# XMOS_TSBOARD_IV.net
KiCad netlist of a schematic drawn in Altium Designer
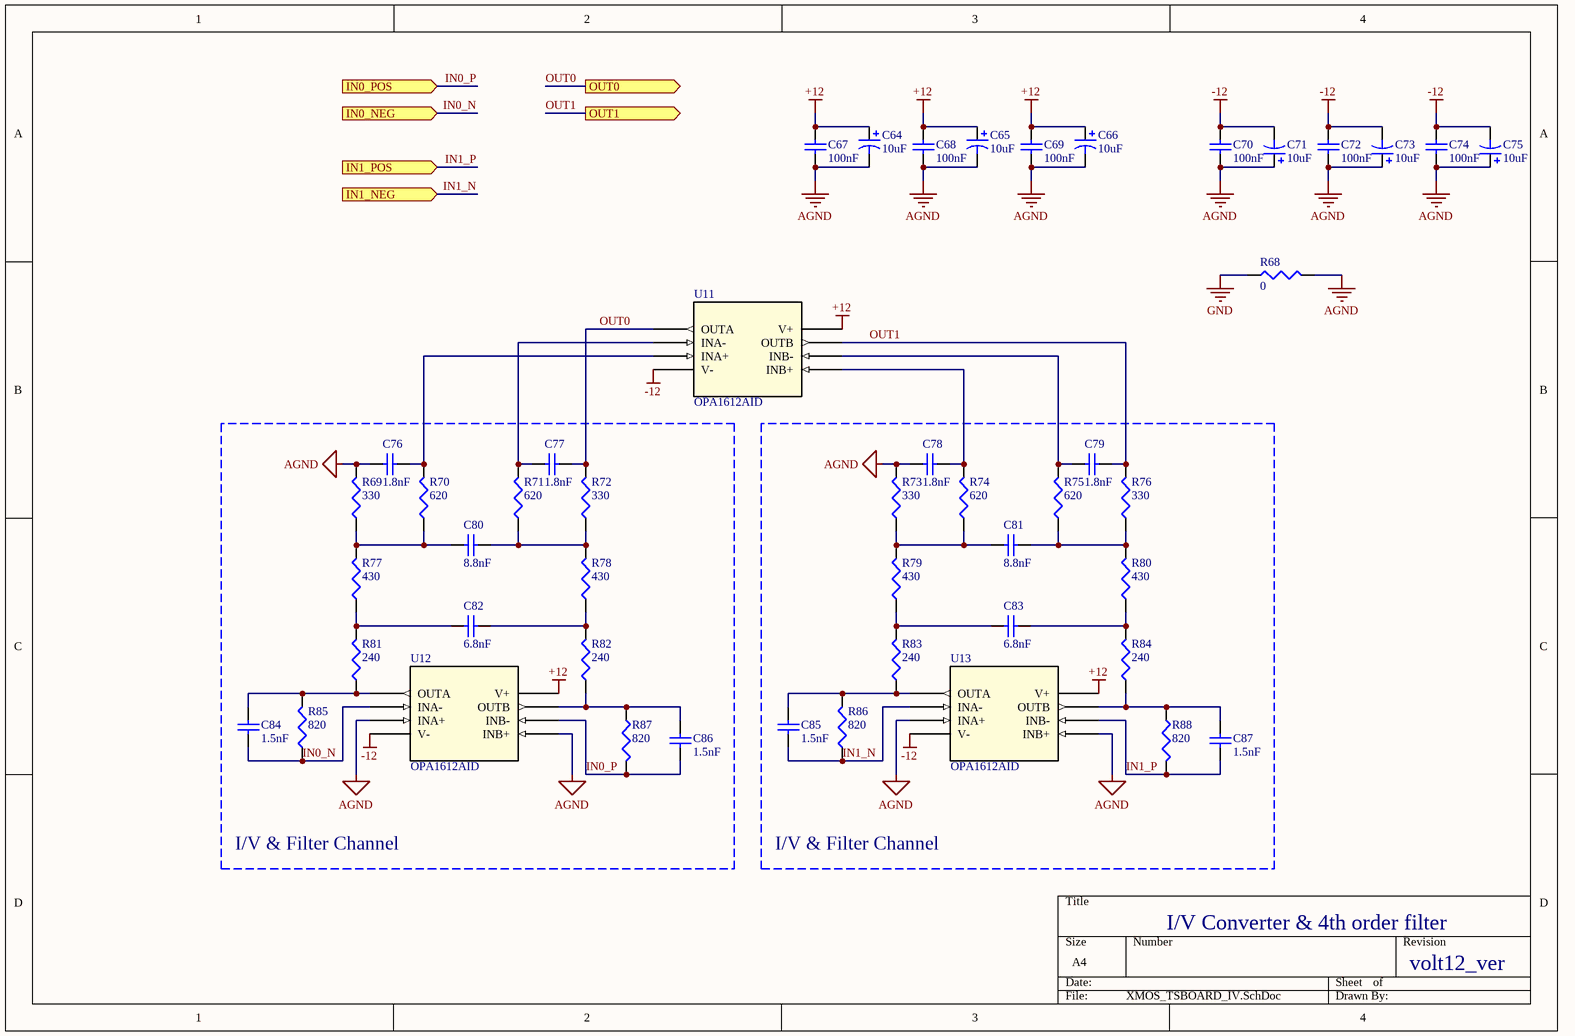
[diagram p0: XMOS_TSBOARD_IV.SchDoc]

(export (version "E")
  (design (tool "Eeschema 10.0.6"))
  (components
    (comp (ref "C64")
      (value "10uF")
      (footprint "C0805")
      (description "Polarized Capacitor (Surface Mount)")
      (fields (field (name "Comment") "Cap Pol3") (field (name "PUBLISHER") "Altium Limited"))
      (libsource (lib "Miscellaneous Devices") (part "Cap Pol3"))
    )
    (comp (ref "C65")
      (value "10uF")
      (footprint "C0805")
      (description "Polarized Capacitor (Surface Mount)")
      (fields (field (name "Comment") "Cap Pol3") (field (name "PUBLISHER") "Altium Limited"))
      (libsource (lib "Miscellaneous Devices") (part "Cap Pol3"))
    )
    (comp (ref "C66")
      (value "10uF")
      (footprint "C0805")
      (description "Polarized Capacitor (Surface Mount)")
      (fields (field (name "Comment") "Cap Pol3") (field (name "PUBLISHER") "Altium Limited"))
      (libsource (lib "Miscellaneous Devices") (part "Cap Pol3"))
    )
    (comp (ref "C67")
      (value "100nF")
      (footprint "1608[0603]")
      (description "Capacitor (Semiconductor SIM Model)")
      (fields (field (name "Comment") "Cap Semi") (field (name "PUBLISHER") "Altium Limited"))
      (libsource (lib "Miscellaneous Devices") (part "Cap Semi"))
    )
    (comp (ref "C68")
      (value "100nF")
      (footprint "1608[0603]")
      (description "Capacitor (Semiconductor SIM Model)")
      (fields (field (name "Comment") "Cap Semi") (field (name "PUBLISHER") "Altium Limited"))
      (libsource (lib "Miscellaneous Devices") (part "Cap Semi"))
    )
    (comp (ref "C69")
      (value "100nF")
      (footprint "1608[0603]")
      (description "Capacitor (Semiconductor SIM Model)")
      (fields (field (name "Comment") "Cap Semi") (field (name "PUBLISHER") "Altium Limited"))
      (libsource (lib "Miscellaneous Devices") (part "Cap Semi"))
    )
    (comp (ref "C70")
      (value "100nF")
      (footprint "1608[0603]")
      (description "Capacitor (Semiconductor SIM Model)")
      (fields (field (name "Comment") "Cap Semi") (field (name "PUBLISHER") "Altium Limited"))
      (libsource (lib "Miscellaneous Devices") (part "Cap Semi"))
    )
    (comp (ref "C71")
      (value "10uF")
      (footprint "C0805")
      (description "Polarized Capacitor (Surface Mount)")
      (fields (field (name "Comment") "Cap Pol3") (field (name "PUBLISHER") "Altium Limited"))
      (libsource (lib "") (part "Cap Pol3_1"))
    )
    (comp (ref "C72")
      (value "100nF")
      (footprint "1608[0603]")
      (description "Capacitor (Semiconductor SIM Model)")
      (fields (field (name "Comment") "Cap Semi") (field (name "PUBLISHER") "Altium Limited"))
      (libsource (lib "Miscellaneous Devices") (part "Cap Semi"))
    )
    (comp (ref "C73")
      (value "10uF")
      (footprint "C0805")
      (description "Polarized Capacitor (Surface Mount)")
      (fields (field (name "Comment") "Cap Pol3") (field (name "PUBLISHER") "Altium Limited"))
      (libsource (lib "") (part "Cap Pol3_1"))
    )
    (comp (ref "C74")
      (value "100nF")
      (footprint "1608[0603]")
      (description "Capacitor (Semiconductor SIM Model)")
      (fields (field (name "Comment") "Cap Semi") (field (name "PUBLISHER") "Altium Limited"))
      (libsource (lib "Miscellaneous Devices") (part "Cap Semi"))
    )
    (comp (ref "C75")
      (value "10uF")
      (footprint "C0805")
      (description "Polarized Capacitor (Surface Mount)")
      (fields (field (name "Comment") "Cap Pol3") (field (name "PUBLISHER") "Altium Limited"))
      (libsource (lib "") (part "Cap Pol3_1"))
    )
    (comp (ref "C76")
      (value "1.8nF")
      (footprint "1608[0603]")
      (description "Capacitor (Semiconductor SIM Model)")
      (fields (field (name "Comment") "Cap Semi") (field (name "PUBLISHER") "Altium Limited"))
      (libsource (lib "Miscellaneous Devices") (part "Cap Semi"))
    )
    (comp (ref "C77")
      (value "1.8nF")
      (footprint "1608[0603]")
      (description "Capacitor (Semiconductor SIM Model)")
      (fields (field (name "Comment") "Cap Semi") (field (name "PUBLISHER") "Altium Limited"))
      (libsource (lib "Miscellaneous Devices") (part "Cap Semi"))
    )
    (comp (ref "C78")
      (value "1.8nF")
      (footprint "1608[0603]")
      (description "Capacitor (Semiconductor SIM Model)")
      (fields (field (name "Comment") "Cap Semi") (field (name "PUBLISHER") "Altium Limited"))
      (libsource (lib "Miscellaneous Devices") (part "Cap Semi"))
    )
    (comp (ref "C79")
      (value "1.8nF")
      (footprint "1608[0603]")
      (description "Capacitor (Semiconductor SIM Model)")
      (fields (field (name "Comment") "Cap Semi") (field (name "PUBLISHER") "Altium Limited"))
      (libsource (lib "Miscellaneous Devices") (part "Cap Semi"))
    )
    (comp (ref "C80")
      (value "8.8nF")
      (footprint "1608[0603]")
      (description "Capacitor (Semiconductor SIM Model)")
      (fields (field (name "Comment") "Cap Semi") (field (name "PUBLISHER") "Altium Limited"))
      (libsource (lib "Miscellaneous Devices") (part "Cap Semi"))
    )
    (comp (ref "C81")
      (value "8.8nF")
      (footprint "1608[0603]")
      (description "Capacitor (Semiconductor SIM Model)")
      (fields (field (name "Comment") "Cap Semi") (field (name "PUBLISHER") "Altium Limited"))
      (libsource (lib "Miscellaneous Devices") (part "Cap Semi"))
    )
    (comp (ref "C82")
      (value "6.8nF")
      (footprint "1608[0603]")
      (description "Capacitor (Semiconductor SIM Model)")
      (fields (field (name "Comment") "Cap Semi") (field (name "PUBLISHER") "Altium Limited"))
      (libsource (lib "Miscellaneous Devices") (part "Cap Semi"))
    )
    (comp (ref "C83")
      (value "6.8nF")
      (footprint "1608[0603]")
      (description "Capacitor (Semiconductor SIM Model)")
      (fields (field (name "Comment") "Cap Semi") (field (name "PUBLISHER") "Altium Limited"))
      (libsource (lib "Miscellaneous Devices") (part "Cap Semi"))
    )
    (comp (ref "C84")
      (value "1.5nF")
      (footprint "1608[0603]")
      (description "Capacitor (Semiconductor SIM Model)")
      (fields (field (name "Comment") "Cap Semi") (field (name "PUBLISHER") "Altium Limited"))
      (libsource (lib "Miscellaneous Devices") (part "Cap Semi"))
    )
    (comp (ref "C85")
      (value "1.5nF")
      (footprint "1608[0603]")
      (description "Capacitor (Semiconductor SIM Model)")
      (fields (field (name "Comment") "Cap Semi") (field (name "PUBLISHER") "Altium Limited"))
      (libsource (lib "Miscellaneous Devices") (part "Cap Semi"))
    )
    (comp (ref "C86")
      (value "1.5nF")
      (footprint "1608[0603]")
      (description "Capacitor (Semiconductor SIM Model)")
      (fields (field (name "Comment") "Cap Semi") (field (name "PUBLISHER") "Altium Limited"))
      (libsource (lib "Miscellaneous Devices") (part "Cap Semi"))
    )
    (comp (ref "C87")
      (value "1.5nF")
      (footprint "1608[0603]")
      (description "Capacitor (Semiconductor SIM Model)")
      (fields (field (name "Comment") "Cap Semi") (field (name "PUBLISHER") "Altium Limited"))
      (libsource (lib "Miscellaneous Devices") (part "Cap Semi"))
    )
    (comp (ref "R68")
      (value "0")
      (footprint "J1-0603")
      (description "Resistor")
      (fields (field (name "Comment") "Res3") (field (name "PUBLISHER") "Altium Limited"))
      (libsource (lib "Miscellaneous Devices") (part "Res3"))
    )
    (comp (ref "R69")
      (value "330")
      (footprint "J1-0603")
      (description "Resistor")
      (fields (field (name "Comment") "Res3") (field (name "PUBLISHER") "Altium Limited"))
      (libsource (lib "Miscellaneous Devices") (part "Res3"))
    )
    (comp (ref "R70")
      (value "620")
      (footprint "J1-0603")
      (description "Resistor")
      (fields (field (name "Comment") "Res3") (field (name "PUBLISHER") "Altium Limited"))
      (libsource (lib "Miscellaneous Devices") (part "Res3"))
    )
    (comp (ref "R71")
      (value "620")
      (footprint "J1-0603")
      (description "Resistor")
      (fields (field (name "Comment") "Res3") (field (name "PUBLISHER") "Altium Limited"))
      (libsource (lib "Miscellaneous Devices") (part "Res3"))
    )
    (comp (ref "R72")
      (value "330")
      (footprint "J1-0603")
      (description "Resistor")
      (fields (field (name "Comment") "Res3") (field (name "PUBLISHER") "Altium Limited"))
      (libsource (lib "Miscellaneous Devices") (part "Res3"))
    )
    (comp (ref "R73")
      (value "330")
      (footprint "J1-0603")
      (description "Resistor")
      (fields (field (name "Comment") "Res3") (field (name "PUBLISHER") "Altium Limited"))
      (libsource (lib "Miscellaneous Devices") (part "Res3"))
    )
    (comp (ref "R74")
      (value "620")
      (footprint "J1-0603")
      (description "Resistor")
      (fields (field (name "Comment") "Res3") (field (name "PUBLISHER") "Altium Limited"))
      (libsource (lib "Miscellaneous Devices") (part "Res3"))
    )
    (comp (ref "R75")
      (value "620")
      (footprint "J1-0603")
      (description "Resistor")
      (fields (field (name "Comment") "Res3") (field (name "PUBLISHER") "Altium Limited"))
      (libsource (lib "Miscellaneous Devices") (part "Res3"))
    )
    (comp (ref "R76")
      (value "330")
      (footprint "J1-0603")
      (description "Resistor")
      (fields (field (name "Comment") "Res3") (field (name "PUBLISHER") "Altium Limited"))
      (libsource (lib "Miscellaneous Devices") (part "Res3"))
    )
    (comp (ref "R77")
      (value "430")
      (footprint "J1-0603")
      (description "Resistor")
      (fields (field (name "Comment") "Res3") (field (name "PUBLISHER") "Altium Limited"))
      (libsource (lib "Miscellaneous Devices") (part "Res3"))
    )
    (comp (ref "R78")
      (value "430")
      (footprint "J1-0603")
      (description "Resistor")
      (fields (field (name "Comment") "Res3") (field (name "PUBLISHER") "Altium Limited"))
      (libsource (lib "Miscellaneous Devices") (part "Res3"))
    )
    (comp (ref "R79")
      (value "430")
      (footprint "J1-0603")
      (description "Resistor")
      (fields (field (name "Comment") "Res3") (field (name "PUBLISHER") "Altium Limited"))
      (libsource (lib "Miscellaneous Devices") (part "Res3"))
    )
    (comp (ref "R80")
      (value "430")
      (footprint "J1-0603")
      (description "Resistor")
      (fields (field (name "Comment") "Res3") (field (name "PUBLISHER") "Altium Limited"))
      (libsource (lib "Miscellaneous Devices") (part "Res3"))
    )
    (comp (ref "R81")
      (value "240")
      (footprint "J1-0603")
      (description "Resistor")
      (fields (field (name "Comment") "Res3") (field (name "PUBLISHER") "Altium Limited"))
      (libsource (lib "Miscellaneous Devices") (part "Res3"))
    )
    (comp (ref "R82")
      (value "240")
      (footprint "J1-0603")
      (description "Resistor")
      (fields (field (name "Comment") "Res3") (field (name "PUBLISHER") "Altium Limited"))
      (libsource (lib "Miscellaneous Devices") (part "Res3"))
    )
    (comp (ref "R83")
      (value "240")
      (footprint "J1-0603")
      (description "Resistor")
      (fields (field (name "Comment") "Res3") (field (name "PUBLISHER") "Altium Limited"))
      (libsource (lib "Miscellaneous Devices") (part "Res3"))
    )
    (comp (ref "R84")
      (value "240")
      (footprint "J1-0603")
      (description "Resistor")
      (fields (field (name "Comment") "Res3") (field (name "PUBLISHER") "Altium Limited"))
      (libsource (lib "Miscellaneous Devices") (part "Res3"))
    )
    (comp (ref "R85")
      (value "820")
      (footprint "J1-0603")
      (description "Resistor")
      (fields (field (name "Comment") "Res3") (field (name "PUBLISHER") "Altium Limited"))
      (libsource (lib "Miscellaneous Devices") (part "Res3"))
    )
    (comp (ref "R86")
      (value "820")
      (footprint "J1-0603")
      (description "Resistor")
      (fields (field (name "Comment") "Res3") (field (name "PUBLISHER") "Altium Limited"))
      (libsource (lib "Miscellaneous Devices") (part "Res3"))
    )
    (comp (ref "R87")
      (value "820")
      (footprint "J1-0603")
      (description "Resistor")
      (fields (field (name "Comment") "Res3") (field (name "PUBLISHER") "Altium Limited"))
      (libsource (lib "Miscellaneous Devices") (part "Res3"))
    )
    (comp (ref "R88")
      (value "820")
      (footprint "J1-0603")
      (description "Resistor")
      (fields (field (name "Comment") "Res3") (field (name "PUBLISHER") "Altium Limited"))
      (libsource (lib "Miscellaneous Devices") (part "Res3"))
    )
    (comp (ref "U11")
      (value "OPA1612AID")
      (footprint "D8")
      (description "SoundPlus High-Performance, Bipolar-Input Audio Operational Amplifiers")
      (libsource (lib "Troposphere_lib") (part "OPA1612AID"))
    )
    (comp (ref "U12")
      (value "OPA1612AID")
      (footprint "D8")
      (description "SoundPlus High-Performance, Bipolar-Input Audio Operational Amplifiers")
      (libsource (lib "Troposphere_lib") (part "OPA1612AID"))
    )
    (comp (ref "U13")
      (value "OPA1612AID")
      (footprint "D8")
      (description "SoundPlus High-Performance, Bipolar-Input Audio Operational Amplifiers")
      (libsource (lib "Troposphere_lib") (part "OPA1612AID"))
    )
  )
  (nets
    (net (code "1") (name "+12") (class "Default")
      (node (ref "C64") (pin "1") (pinfunction "1_1") (pintype "passive"))
      (node (ref "C65") (pin "1") (pinfunction "1_1") (pintype "passive"))
      (node (ref "C66") (pin "1") (pinfunction "1_1") (pintype "passive"))
      (node (ref "C67") (pin "2") (pinfunction "2_2") (pintype "passive"))
      (node (ref "C68") (pin "2") (pinfunction "2_2") (pintype "passive"))
      (node (ref "C69") (pin "2") (pinfunction "2_2") (pintype "passive"))
      (node (ref "U11") (pin "8") (pinfunction "V+_8") (pintype "power_in"))
      (node (ref "U12") (pin "8") (pinfunction "V+_8") (pintype "power_in"))
      (node (ref "U13") (pin "8") (pinfunction "V+_8") (pintype "power_in"))
    )
    (net (code "2") (name "-12") (class "Default")
      (node (ref "C70") (pin "2") (pinfunction "2_2") (pintype "passive"))
      (node (ref "C71") (pin "2") (pinfunction "2_2") (pintype "passive"))
      (node (ref "C72") (pin "2") (pinfunction "2_2") (pintype "passive"))
      (node (ref "C73") (pin "2") (pinfunction "2_2") (pintype "passive"))
      (node (ref "C74") (pin "2") (pinfunction "2_2") (pintype "passive"))
      (node (ref "C75") (pin "2") (pinfunction "2_2") (pintype "passive"))
      (node (ref "U11") (pin "4") (pinfunction "V-_4") (pintype "power_in"))
      (node (ref "U12") (pin "4") (pinfunction "V-_4") (pintype "power_in"))
      (node (ref "U13") (pin "4") (pinfunction "V-_4") (pintype "power_in"))
    )
    (net (code "3") (name "/IN0_N") (class "Default")
      (node (ref "C84") (pin "1") (pinfunction "1_1") (pintype "passive"))
      (node (ref "R85") (pin "1") (pinfunction "1_1") (pintype "passive"))
      (node (ref "U12") (pin "2") (pinfunction "INA-_2") (pintype "input"))
    )
    (net (code "4") (name "/IN0_P") (class "Default")
      (node (ref "C86") (pin "2") (pinfunction "2_2") (pintype "passive"))
      (node (ref "R87") (pin "2") (pinfunction "2_2") (pintype "passive"))
      (node (ref "U12") (pin "6") (pinfunction "INB-_6") (pintype "input"))
    )
    (net (code "5") (name "/IN1_N") (class "Default")
      (node (ref "C85") (pin "1") (pinfunction "1_1") (pintype "passive"))
      (node (ref "R86") (pin "1") (pinfunction "1_1") (pintype "passive"))
      (node (ref "U13") (pin "2") (pinfunction "INA-_2") (pintype "input"))
    )
    (net (code "6") (name "/IN1_P") (class "Default")
      (node (ref "C87") (pin "2") (pinfunction "2_2") (pintype "passive"))
      (node (ref "R88") (pin "2") (pinfunction "2_2") (pintype "passive"))
      (node (ref "U13") (pin "6") (pinfunction "INB-_6") (pintype "input"))
    )
    (net (code "7") (name "/OUT0") (class "Default")
      (node (ref "C77") (pin "1") (pinfunction "1_1") (pintype "passive"))
      (node (ref "R72") (pin "2") (pinfunction "2_2") (pintype "passive"))
      (node (ref "U11") (pin "1") (pinfunction "OUTA_1") (pintype "output"))
    )
    (net (code "8") (name "/OUT1") (class "Default")
      (node (ref "C79") (pin "1") (pinfunction "1_1") (pintype "passive"))
      (node (ref "R76") (pin "2") (pinfunction "2_2") (pintype "passive"))
      (node (ref "U11") (pin "7") (pinfunction "OUTB_7") (pintype "output"))
    )
    (net (code "9") (name "AGND") (class "Default")
      (node (ref "C64") (pin "2") (pinfunction "2_2") (pintype "passive"))
      (node (ref "C65") (pin "2") (pinfunction "2_2") (pintype "passive"))
      (node (ref "C66") (pin "2") (pinfunction "2_2") (pintype "passive"))
      (node (ref "C67") (pin "1") (pinfunction "1_1") (pintype "passive"))
      (node (ref "C68") (pin "1") (pinfunction "1_1") (pintype "passive"))
      (node (ref "C69") (pin "1") (pinfunction "1_1") (pintype "passive"))
      (node (ref "C70") (pin "1") (pinfunction "1_1") (pintype "passive"))
      (node (ref "C71") (pin "1") (pinfunction "1_1") (pintype "passive"))
      (node (ref "C72") (pin "1") (pinfunction "1_1") (pintype "passive"))
      (node (ref "C73") (pin "1") (pinfunction "1_1") (pintype "passive"))
      (node (ref "C74") (pin "1") (pinfunction "1_1") (pintype "passive"))
      (node (ref "C75") (pin "1") (pinfunction "1_1") (pintype "passive"))
      (node (ref "C76") (pin "2") (pinfunction "2_2") (pintype "passive"))
      (node (ref "C78") (pin "2") (pinfunction "2_2") (pintype "passive"))
      (node (ref "R68") (pin "2") (pinfunction "2_2") (pintype "passive"))
      (node (ref "R69") (pin "2") (pinfunction "2_2") (pintype "passive"))
      (node (ref "R73") (pin "2") (pinfunction "2_2") (pintype "passive"))
      (node (ref "U12") (pin "3") (pinfunction "INA+_3") (pintype "input"))
      (node (ref "U12") (pin "5") (pinfunction "INB+_5") (pintype "input"))
      (node (ref "U13") (pin "3") (pinfunction "INA+_3") (pintype "input"))
      (node (ref "U13") (pin "5") (pinfunction "INB+_5") (pintype "input"))
    )
    (net (code "10") (name "GND") (class "Default")
      (node (ref "R68") (pin "1") (pinfunction "1_1") (pintype "passive"))
    )
    (net (code "11") (name "Net-(C80-Pad1)") (class "Default")
      (node (ref "C80") (pin "1") (pinfunction "1_1") (pintype "passive"))
      (node (ref "R71") (pin "1") (pinfunction "1_1") (pintype "passive"))
      (node (ref "R72") (pin "1") (pinfunction "1_1") (pintype "passive"))
      (node (ref "R78") (pin "2") (pinfunction "2_2") (pintype "passive"))
    )
    (net (code "12") (name "Net-(C80-Pad2)") (class "Default")
      (node (ref "C80") (pin "2") (pinfunction "2_2") (pintype "passive"))
      (node (ref "R69") (pin "1") (pinfunction "1_1") (pintype "passive"))
      (node (ref "R70") (pin "1") (pinfunction "1_1") (pintype "passive"))
      (node (ref "R77") (pin "2") (pinfunction "2_2") (pintype "passive"))
    )
    (net (code "13") (name "Net-(C81-Pad1)") (class "Default")
      (node (ref "C81") (pin "1") (pinfunction "1_1") (pintype "passive"))
      (node (ref "R75") (pin "1") (pinfunction "1_1") (pintype "passive"))
      (node (ref "R76") (pin "1") (pinfunction "1_1") (pintype "passive"))
      (node (ref "R80") (pin "2") (pinfunction "2_2") (pintype "passive"))
    )
    (net (code "14") (name "Net-(C81-Pad2)") (class "Default")
      (node (ref "C81") (pin "2") (pinfunction "2_2") (pintype "passive"))
      (node (ref "R73") (pin "1") (pinfunction "1_1") (pintype "passive"))
      (node (ref "R74") (pin "1") (pinfunction "1_1") (pintype "passive"))
      (node (ref "R79") (pin "2") (pinfunction "2_2") (pintype "passive"))
    )
    (net (code "15") (name "Net-(C82-Pad1)") (class "Default")
      (node (ref "C82") (pin "1") (pinfunction "1_1") (pintype "passive"))
      (node (ref "R78") (pin "1") (pinfunction "1_1") (pintype "passive"))
      (node (ref "R82") (pin "2") (pinfunction "2_2") (pintype "passive"))
    )
    (net (code "16") (name "Net-(C82-Pad2)") (class "Default")
      (node (ref "C82") (pin "2") (pinfunction "2_2") (pintype "passive"))
      (node (ref "R77") (pin "1") (pinfunction "1_1") (pintype "passive"))
      (node (ref "R81") (pin "2") (pinfunction "2_2") (pintype "passive"))
    )
    (net (code "17") (name "Net-(C83-Pad1)") (class "Default")
      (node (ref "C83") (pin "1") (pinfunction "1_1") (pintype "passive"))
      (node (ref "R80") (pin "1") (pinfunction "1_1") (pintype "passive"))
      (node (ref "R84") (pin "2") (pinfunction "2_2") (pintype "passive"))
    )
    (net (code "18") (name "Net-(C83-Pad2)") (class "Default")
      (node (ref "C83") (pin "2") (pinfunction "2_2") (pintype "passive"))
      (node (ref "R79") (pin "1") (pinfunction "1_1") (pintype "passive"))
      (node (ref "R83") (pin "2") (pinfunction "2_2") (pintype "passive"))
    )
    (net (code "19") (name "Net-(U11-INA+)") (class "Default")
      (node (ref "C76") (pin "1") (pinfunction "1_1") (pintype "passive"))
      (node (ref "R70") (pin "2") (pinfunction "2_2") (pintype "passive"))
      (node (ref "U11") (pin "3") (pinfunction "INA+_3") (pintype "input"))
    )
    (net (code "20") (name "Net-(U11-INA-)") (class "Default")
      (node (ref "C77") (pin "2") (pinfunction "2_2") (pintype "passive"))
      (node (ref "R71") (pin "2") (pinfunction "2_2") (pintype "passive"))
      (node (ref "U11") (pin "2") (pinfunction "INA-_2") (pintype "input"))
    )
    (net (code "21") (name "Net-(U11-INB+)") (class "Default")
      (node (ref "C78") (pin "1") (pinfunction "1_1") (pintype "passive"))
      (node (ref "R74") (pin "2") (pinfunction "2_2") (pintype "passive"))
      (node (ref "U11") (pin "5") (pinfunction "INB+_5") (pintype "input"))
    )
    (net (code "22") (name "Net-(U11-INB-)") (class "Default")
      (node (ref "C79") (pin "2") (pinfunction "2_2") (pintype "passive"))
      (node (ref "R75") (pin "2") (pinfunction "2_2") (pintype "passive"))
      (node (ref "U11") (pin "6") (pinfunction "INB-_6") (pintype "input"))
    )
    (net (code "23") (name "Net-(U12-OUTA)") (class "Default")
      (node (ref "C84") (pin "2") (pinfunction "2_2") (pintype "passive"))
      (node (ref "R81") (pin "1") (pinfunction "1_1") (pintype "passive"))
      (node (ref "R85") (pin "2") (pinfunction "2_2") (pintype "passive"))
      (node (ref "U12") (pin "1") (pinfunction "OUTA_1") (pintype "output"))
    )
    (net (code "24") (name "Net-(U12-OUTB)") (class "Default")
      (node (ref "C86") (pin "1") (pinfunction "1_1") (pintype "passive"))
      (node (ref "R82") (pin "1") (pinfunction "1_1") (pintype "passive"))
      (node (ref "R87") (pin "1") (pinfunction "1_1") (pintype "passive"))
      (node (ref "U12") (pin "7") (pinfunction "OUTB_7") (pintype "output"))
    )
    (net (code "25") (name "Net-(U13-OUTA)") (class "Default")
      (node (ref "C85") (pin "2") (pinfunction "2_2") (pintype "passive"))
      (node (ref "R83") (pin "1") (pinfunction "1_1") (pintype "passive"))
      (node (ref "R86") (pin "2") (pinfunction "2_2") (pintype "passive"))
      (node (ref "U13") (pin "1") (pinfunction "OUTA_1") (pintype "output"))
    )
    (net (code "26") (name "Net-(U13-OUTB)") (class "Default")
      (node (ref "C87") (pin "1") (pinfunction "1_1") (pintype "passive"))
      (node (ref "R84") (pin "1") (pinfunction "1_1") (pintype "passive"))
      (node (ref "R88") (pin "1") (pinfunction "1_1") (pintype "passive"))
      (node (ref "U13") (pin "7") (pinfunction "OUTB_7") (pintype "output"))
    )
  )
)
